# CAN-SW.net
KiCad netlist of a schematic drawn in Altium Designer
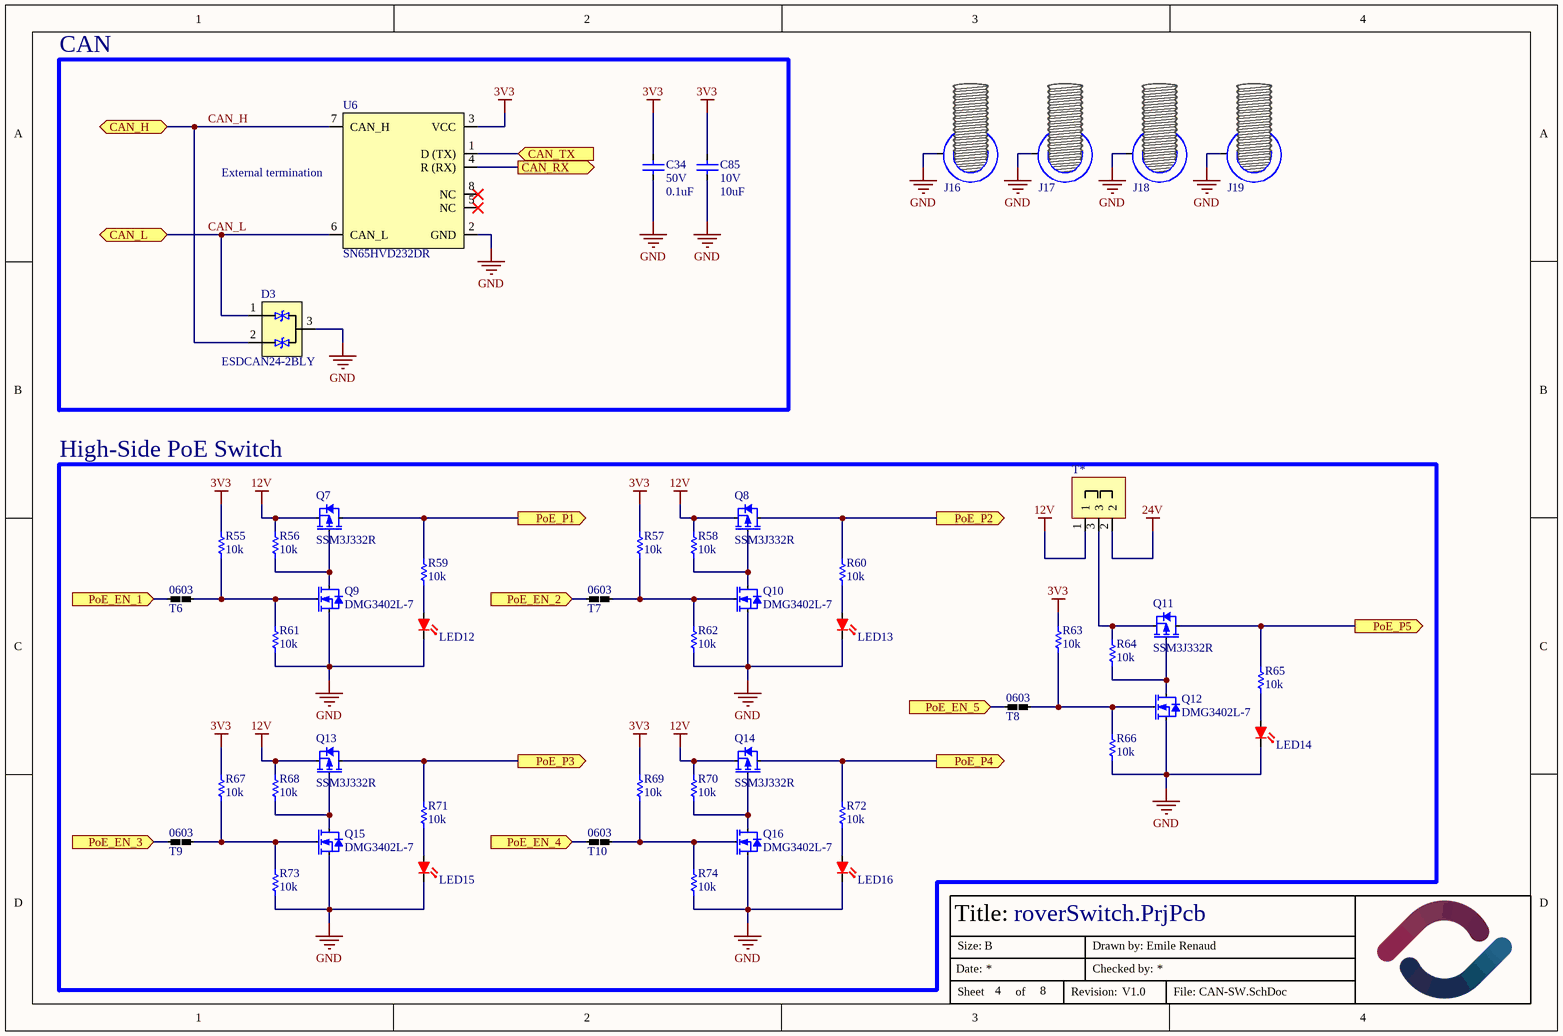
[diagram p0: CAN-SW.SchDoc]

(export (version "E")
  (design (tool "Eeschema 10.0.6"))
  (components
    (comp (ref "C34")
      (value "0.1uF")
      (footprint "CAPACITOR-0603")
      (description "Capacitor-0603-0.1uF-50V-X7R")
      (fields (field (name "VOLT") "50V"))
      (libsource (lib "Capacitors") (part "Capacitor-0603-0.1uF-50V-X7R"))
    )
    (comp (ref "C85")
      (value "10uF")
      (footprint "CAPACITOR-0603")
      (description "10 µF ±20% 10V Ceramic Capacitor X5R 0603 (1608 Metric)")
      (fields (field (name "VOLT") "10V") (field (name "Comment") "Capacitor-0603-10uF-10V-X5R"))
      (libsource (lib "Capacitors") (part "Capacitor-0603-10uF-10V-X5R"))
    )
    (comp (ref "D3")
      (value "ESDCAN24-2BLY")
      (footprint "SOT-23-3")
      (description "55V Clamp 6A (8/20µs) Ipp Tvs Diode Surface Mount SOT-23")
      (libsource (lib "diodes-tvs") (part "ESDCAN24-2BLY"))
    )
    (comp (ref "J16")
      (value "hole")
      (footprint "HOLE-3.40MM-M3-8MMEYELET")
      (description "Hole for M3 Bolt with 8mm pad")
      (libsource (lib "JumpersAndHoles") (part "Hole 3.40mm M3-Eyelet"))
    )
    (comp (ref "J17")
      (value "hole")
      (footprint "HOLE-3.40MM-M3-8MMEYELET")
      (description "Hole for M3 Bolt with 8mm pad")
      (libsource (lib "JumpersAndHoles") (part "Hole 3.40mm M3-Eyelet"))
    )
    (comp (ref "J18")
      (value "hole")
      (footprint "HOLE-3.40MM-M3-8MMEYELET")
      (description "Hole for M3 Bolt with 8mm pad")
      (libsource (lib "JumpersAndHoles") (part "Hole 3.40mm M3-Eyelet"))
    )
    (comp (ref "J19")
      (value "hole")
      (footprint "HOLE-3.40MM-M3-8MMEYELET")
      (description "Hole for M3 Bolt with 8mm pad")
      (libsource (lib "JumpersAndHoles") (part "Hole 3.40mm M3-Eyelet"))
    )
    (comp (ref "LED12")
      (value "B1911USD-20D000114U1930")
      (footprint "LED-0603-2PIN")
      (description "LED RED CLEAR 0603 SMD")
      (libsource (lib "LEDs") (part "B1911USD-20D000114U1930"))
    )
    (comp (ref "LED13")
      (value "B1911USD-20D000114U1930")
      (footprint "LED-0603-2PIN")
      (description "LED RED CLEAR 0603 SMD")
      (libsource (lib "LEDs") (part "B1911USD-20D000114U1930"))
    )
    (comp (ref "LED14")
      (value "B1911USD-20D000114U1930")
      (footprint "LED-0603-2PIN")
      (description "LED RED CLEAR 0603 SMD")
      (libsource (lib "LEDs") (part "B1911USD-20D000114U1930"))
    )
    (comp (ref "LED15")
      (value "B1911USD-20D000114U1930")
      (footprint "LED-0603-2PIN")
      (description "LED RED CLEAR 0603 SMD")
      (libsource (lib "LEDs") (part "B1911USD-20D000114U1930"))
    )
    (comp (ref "LED16")
      (value "B1911USD-20D000114U1930")
      (footprint "LED-0603-2PIN")
      (description "LED RED CLEAR 0603 SMD")
      (libsource (lib "LEDs") (part "B1911USD-20D000114U1930"))
    )
    (comp (ref "Q7")
      (value "SSM3J332R")
      (footprint "SOT-23-3")
      (description "P-Channel 30 V 6A (Ta) 1W (Ta) Surface Mount SOT-23F")
      (libsource (lib "FET-P-Small") (part "SSM3J332R"))
    )
    (comp (ref "Q8")
      (value "SSM3J332R")
      (footprint "SOT-23-3")
      (description "P-Channel 30 V 6A (Ta) 1W (Ta) Surface Mount SOT-23F")
      (libsource (lib "FET-P-Small") (part "SSM3J332R"))
    )
    (comp (ref "Q9")
      (value "DMG3402L-7")
      (footprint "SOT-23-3")
      (description "N-Channel 30 V 4A (Ta) 1.4W (Ta) Surface Mount SOT-23-3")
      (libsource (lib "FET-N-Small") (part "DMG3402L-7"))
    )
    (comp (ref "Q10")
      (value "DMG3402L-7")
      (footprint "SOT-23-3")
      (description "N-Channel 30 V 4A (Ta) 1.4W (Ta) Surface Mount SOT-23-3")
      (libsource (lib "FET-N-Small") (part "DMG3402L-7"))
    )
    (comp (ref "Q11")
      (value "SSM3J332R")
      (footprint "SOT-23-3")
      (description "P-Channel 30 V 6A (Ta) 1W (Ta) Surface Mount SOT-23F")
      (libsource (lib "FET-P-Small") (part "SSM3J332R"))
    )
    (comp (ref "Q12")
      (value "DMG3402L-7")
      (footprint "SOT-23-3")
      (description "N-Channel 30 V 4A (Ta) 1.4W (Ta) Surface Mount SOT-23-3")
      (libsource (lib "FET-N-Small") (part "DMG3402L-7"))
    )
    (comp (ref "Q13")
      (value "SSM3J332R")
      (footprint "SOT-23-3")
      (description "P-Channel 30 V 6A (Ta) 1W (Ta) Surface Mount SOT-23F")
      (libsource (lib "FET-P-Small") (part "SSM3J332R"))
    )
    (comp (ref "Q14")
      (value "SSM3J332R")
      (footprint "SOT-23-3")
      (description "P-Channel 30 V 6A (Ta) 1W (Ta) Surface Mount SOT-23F")
      (libsource (lib "FET-P-Small") (part "SSM3J332R"))
    )
    (comp (ref "Q15")
      (value "DMG3402L-7")
      (footprint "SOT-23-3")
      (description "N-Channel 30 V 4A (Ta) 1.4W (Ta) Surface Mount SOT-23-3")
      (libsource (lib "FET-N-Small") (part "DMG3402L-7"))
    )
    (comp (ref "Q16")
      (value "DMG3402L-7")
      (footprint "SOT-23-3")
      (description "N-Channel 30 V 4A (Ta) 1.4W (Ta) Surface Mount SOT-23-3")
      (libsource (lib "FET-N-Small") (part "DMG3402L-7"))
    )
    (comp (ref "R55")
      (value "10k")
      (footprint "Resistor-0603")
      (description "Resistor0603-10k")
      (fields (field (name "Comment") "SMT resistor"))
      (libsource (lib "Resistors") (part "Resistor-0603-10k"))
    )
    (comp (ref "R56")
      (value "10k")
      (footprint "Resistor-0603")
      (description "Resistor0603-10k")
      (fields (field (name "Comment") "SMT resistor"))
      (libsource (lib "Resistors") (part "Resistor-0603-10k"))
    )
    (comp (ref "R57")
      (value "10k")
      (footprint "Resistor-0603")
      (description "Resistor0603-10k")
      (fields (field (name "Comment") "SMT resistor"))
      (libsource (lib "Resistors") (part "Resistor-0603-10k"))
    )
    (comp (ref "R58")
      (value "10k")
      (footprint "Resistor-0603")
      (description "Resistor0603-10k")
      (fields (field (name "Comment") "SMT resistor"))
      (libsource (lib "Resistors") (part "Resistor-0603-10k"))
    )
    (comp (ref "R59")
      (value "10k")
      (footprint "Resistor-0603")
      (description "Resistor0603-10k")
      (fields (field (name "Comment") "SMT resistor"))
      (libsource (lib "Resistors") (part "Resistor-0603-10k"))
    )
    (comp (ref "R60")
      (value "10k")
      (footprint "Resistor-0603")
      (description "Resistor0603-10k")
      (fields (field (name "Comment") "SMT resistor"))
      (libsource (lib "Resistors") (part "Resistor-0603-10k"))
    )
    (comp (ref "R61")
      (value "10k")
      (footprint "Resistor-0603")
      (description "Resistor0603-10k")
      (fields (field (name "Comment") "SMT resistor"))
      (libsource (lib "Resistors") (part "Resistor-0603-10k"))
    )
    (comp (ref "R62")
      (value "10k")
      (footprint "Resistor-0603")
      (description "Resistor0603-10k")
      (fields (field (name "Comment") "SMT resistor"))
      (libsource (lib "Resistors") (part "Resistor-0603-10k"))
    )
    (comp (ref "R63")
      (value "10k")
      (footprint "Resistor-0603")
      (description "Resistor0603-10k")
      (fields (field (name "Comment") "SMT resistor"))
      (libsource (lib "Resistors") (part "Resistor-0603-10k"))
    )
    (comp (ref "R64")
      (value "10k")
      (footprint "Resistor-0603")
      (description "Resistor0603-10k")
      (fields (field (name "Comment") "SMT resistor"))
      (libsource (lib "Resistors") (part "Resistor-0603-10k"))
    )
    (comp (ref "R65")
      (value "10k")
      (footprint "Resistor-0603")
      (description "Resistor0603-10k")
      (fields (field (name "Comment") "SMT resistor"))
      (libsource (lib "Resistors") (part "Resistor-0603-10k"))
    )
    (comp (ref "R66")
      (value "10k")
      (footprint "Resistor-0603")
      (description "Resistor0603-10k")
      (fields (field (name "Comment") "SMT resistor"))
      (libsource (lib "Resistors") (part "Resistor-0603-10k"))
    )
    (comp (ref "R67")
      (value "10k")
      (footprint "Resistor-0603")
      (description "Resistor0603-10k")
      (fields (field (name "Comment") "SMT resistor"))
      (libsource (lib "Resistors") (part "Resistor-0603-10k"))
    )
    (comp (ref "R68")
      (value "10k")
      (footprint "Resistor-0603")
      (description "Resistor0603-10k")
      (fields (field (name "Comment") "SMT resistor"))
      (libsource (lib "Resistors") (part "Resistor-0603-10k"))
    )
    (comp (ref "R69")
      (value "10k")
      (footprint "Resistor-0603")
      (description "Resistor0603-10k")
      (fields (field (name "Comment") "SMT resistor"))
      (libsource (lib "Resistors") (part "Resistor-0603-10k"))
    )
    (comp (ref "R70")
      (value "10k")
      (footprint "Resistor-0603")
      (description "Resistor0603-10k")
      (fields (field (name "Comment") "SMT resistor"))
      (libsource (lib "Resistors") (part "Resistor-0603-10k"))
    )
    (comp (ref "R71")
      (value "10k")
      (footprint "Resistor-0603")
      (description "Resistor0603-10k")
      (fields (field (name "Comment") "SMT resistor"))
      (libsource (lib "Resistors") (part "Resistor-0603-10k"))
    )
    (comp (ref "R72")
      (value "10k")
      (footprint "Resistor-0603")
      (description "Resistor0603-10k")
      (fields (field (name "Comment") "SMT resistor"))
      (libsource (lib "Resistors") (part "Resistor-0603-10k"))
    )
    (comp (ref "R73")
      (value "10k")
      (footprint "Resistor-0603")
      (description "Resistor0603-10k")
      (fields (field (name "Comment") "SMT resistor"))
      (libsource (lib "Resistors") (part "Resistor-0603-10k"))
    )
    (comp (ref "R74")
      (value "10k")
      (footprint "Resistor-0603")
      (description "Resistor0603-10k")
      (fields (field (name "Comment") "SMT resistor"))
      (libsource (lib "Resistors") (part "Resistor-0603-10k"))
    )
    (comp (ref "T*")
      (value "Jumper-3pos-small")
      (footprint "Jumper-3pos-small")
      (libsource (lib "JumpersAndHoles") (part "Jumper-3pos-small"))
    )
    (comp (ref "T6")
      (value "NetTie_0603_Short")
      (footprint "NetTie-0603-short")
      (libsource (lib "JumpersAndHoles") (part "NetTie_0603_Short"))
    )
    (comp (ref "T7")
      (value "NetTie_0603_Short")
      (footprint "NetTie-0603-short")
      (libsource (lib "JumpersAndHoles") (part "NetTie_0603_Short"))
    )
    (comp (ref "T8")
      (value "NetTie_0603_Short")
      (footprint "NetTie-0603-short")
      (libsource (lib "JumpersAndHoles") (part "NetTie_0603_Short"))
    )
    (comp (ref "T9")
      (value "NetTie_0603_Short")
      (footprint "NetTie-0603-short")
      (libsource (lib "JumpersAndHoles") (part "NetTie_0603_Short"))
    )
    (comp (ref "T10")
      (value "NetTie_0603_Short")
      (footprint "NetTie-0603-short")
      (libsource (lib "JumpersAndHoles") (part "NetTie_0603_Short"))
    )
    (comp (ref "U6")
      (value "SN65HVD232DR")
      (footprint "SOIC-8")
      (description "1/1 Transceiver Half CANbus 8-SOIC")
      (libsource (lib "Transceiver") (part "SN65HVD232DR"))
    )
  )
  (nets
    (net (code "1") (name "/CAN_H") (class "Default")
      (node (ref "D3") (pin "2") (pinfunction "GND_2") (pintype "passive"))
      (node (ref "U6") (pin "7") (pinfunction "CAN_H_7") (pintype "passive"))
    )
    (net (code "2") (name "/CAN_L") (class "Default")
      (node (ref "D3") (pin "1") (pinfunction "L2_1") (pintype "passive"))
      (node (ref "U6") (pin "6") (pinfunction "CAN_L_6") (pintype "passive"))
    )
    (net (code "3") (name "/CAN_RX") (class "Default")
      (node (ref "U6") (pin "4") (pinfunction "R_(RX)_4") (pintype "passive"))
    )
    (net (code "4") (name "/CAN_TX") (class "Default")
      (node (ref "U6") (pin "1") (pinfunction "D_(TX)_1") (pintype "passive"))
    )
    (net (code "5") (name "/PoE_EN_1") (class "Default")
      (node (ref "T6") (pin "2") (pinfunction "2_2") (pintype "passive"))
    )
    (net (code "6") (name "/PoE_EN_2") (class "Default")
      (node (ref "T7") (pin "2") (pinfunction "2_2") (pintype "passive"))
    )
    (net (code "7") (name "/PoE_EN_3") (class "Default")
      (node (ref "T9") (pin "2") (pinfunction "2_2") (pintype "passive"))
    )
    (net (code "8") (name "/PoE_EN_4") (class "Default")
      (node (ref "T10") (pin "2") (pinfunction "2_2") (pintype "passive"))
    )
    (net (code "9") (name "/PoE_EN_5") (class "Default")
      (node (ref "T8") (pin "2") (pinfunction "2_2") (pintype "passive"))
    )
    (net (code "10") (name "/PoE_P1") (class "Default")
      (node (ref "Q7") (pin "3") (pinfunction "D_3") (pintype "passive"))
      (node (ref "R59") (pin "2") (pinfunction "2_2") (pintype "passive"))
    )
    (net (code "11") (name "/PoE_P2") (class "Default")
      (node (ref "Q8") (pin "3") (pinfunction "D_3") (pintype "passive"))
      (node (ref "R60") (pin "2") (pinfunction "2_2") (pintype "passive"))
    )
    (net (code "12") (name "/PoE_P3") (class "Default")
      (node (ref "Q13") (pin "3") (pinfunction "D_3") (pintype "passive"))
      (node (ref "R71") (pin "2") (pinfunction "2_2") (pintype "passive"))
    )
    (net (code "13") (name "/PoE_P4") (class "Default")
      (node (ref "Q14") (pin "3") (pinfunction "D_3") (pintype "passive"))
      (node (ref "R72") (pin "2") (pinfunction "2_2") (pintype "passive"))
    )
    (net (code "14") (name "/PoE_P5") (class "Default")
      (node (ref "Q11") (pin "3") (pinfunction "D_3") (pintype "passive"))
      (node (ref "R65") (pin "2") (pinfunction "2_2") (pintype "passive"))
    )
    (net (code "15") (name "3V3") (class "Default")
      (node (ref "C34") (pin "2") (pinfunction "2_2") (pintype "passive"))
      (node (ref "C85") (pin "2") (pinfunction "2_2") (pintype "passive"))
      (node (ref "R55") (pin "2") (pinfunction "2_2") (pintype "passive"))
      (node (ref "R57") (pin "2") (pinfunction "2_2") (pintype "passive"))
      (node (ref "R63") (pin "2") (pinfunction "2_2") (pintype "passive"))
      (node (ref "R67") (pin "2") (pinfunction "2_2") (pintype "passive"))
      (node (ref "R69") (pin "2") (pinfunction "2_2") (pintype "passive"))
      (node (ref "U6") (pin "3") (pinfunction "VCC_3") (pintype "passive"))
    )
    (net (code "16") (name "12V") (class "Default")
      (node (ref "Q13") (pin "2") (pinfunction "S_2") (pintype "passive"))
      (node (ref "Q14") (pin "2") (pinfunction "S_2") (pintype "passive"))
      (node (ref "Q7") (pin "2") (pinfunction "S_2") (pintype "passive"))
      (node (ref "Q8") (pin "2") (pinfunction "S_2") (pintype "passive"))
      (node (ref "R56") (pin "2") (pinfunction "2_2") (pintype "passive"))
      (node (ref "R58") (pin "2") (pinfunction "2_2") (pintype "passive"))
      (node (ref "R68") (pin "2") (pinfunction "2_2") (pintype "passive"))
      (node (ref "R70") (pin "2") (pinfunction "2_2") (pintype "passive"))
      (node (ref "T*") (pin "1") (pinfunction "1_1") (pintype "passive"))
    )
    (net (code "17") (name "24V") (class "Default")
      (node (ref "T*") (pin "2") (pinfunction "2_2") (pintype "passive"))
    )
    (net (code "18") (name "GND") (class "Default")
      (node (ref "C34") (pin "1") (pinfunction "1_1") (pintype "passive"))
      (node (ref "C85") (pin "1") (pinfunction "1_1") (pintype "passive"))
      (node (ref "D3") (pin "3") (pinfunction "L3_3") (pintype "passive"))
      (node (ref "J16") (pin "1") (pinfunction "1_1") (pintype "passive"))
      (node (ref "J17") (pin "1") (pinfunction "1_1") (pintype "passive"))
      (node (ref "J18") (pin "1") (pinfunction "1_1") (pintype "passive"))
      (node (ref "J19") (pin "1") (pinfunction "1_1") (pintype "passive"))
      (node (ref "LED12") (pin "1") (pinfunction "K_1") (pintype "passive"))
      (node (ref "LED13") (pin "1") (pinfunction "K_1") (pintype "passive"))
      (node (ref "LED14") (pin "1") (pinfunction "K_1") (pintype "passive"))
      (node (ref "LED15") (pin "1") (pinfunction "K_1") (pintype "passive"))
      (node (ref "LED16") (pin "1") (pinfunction "K_1") (pintype "passive"))
      (node (ref "Q10") (pin "2") (pinfunction "S_2") (pintype "passive"))
      (node (ref "Q12") (pin "2") (pinfunction "S_2") (pintype "passive"))
      (node (ref "Q15") (pin "2") (pinfunction "S_2") (pintype "passive"))
      (node (ref "Q16") (pin "2") (pinfunction "S_2") (pintype "passive"))
      (node (ref "Q9") (pin "2") (pinfunction "S_2") (pintype "passive"))
      (node (ref "R61") (pin "1") (pinfunction "1_1") (pintype "passive"))
      (node (ref "R62") (pin "1") (pinfunction "1_1") (pintype "passive"))
      (node (ref "R66") (pin "1") (pinfunction "1_1") (pintype "passive"))
      (node (ref "R73") (pin "1") (pinfunction "1_1") (pintype "passive"))
      (node (ref "R74") (pin "1") (pinfunction "1_1") (pintype "passive"))
      (node (ref "U6") (pin "2") (pinfunction "GND_2") (pintype "passive"))
    )
    (net (code "19") (name "Net-(LED12-R)") (class "Default")
      (node (ref "LED12") (pin "2") (pinfunction "R_2") (pintype "passive"))
      (node (ref "R59") (pin "1") (pinfunction "1_1") (pintype "passive"))
    )
    (net (code "20") (name "Net-(LED13-R)") (class "Default")
      (node (ref "LED13") (pin "2") (pinfunction "R_2") (pintype "passive"))
      (node (ref "R60") (pin "1") (pinfunction "1_1") (pintype "passive"))
    )
    (net (code "21") (name "Net-(LED14-R)") (class "Default")
      (node (ref "LED14") (pin "2") (pinfunction "R_2") (pintype "passive"))
      (node (ref "R65") (pin "1") (pinfunction "1_1") (pintype "passive"))
    )
    (net (code "22") (name "Net-(LED15-R)") (class "Default")
      (node (ref "LED15") (pin "2") (pinfunction "R_2") (pintype "passive"))
      (node (ref "R71") (pin "1") (pinfunction "1_1") (pintype "passive"))
    )
    (net (code "23") (name "Net-(LED16-R)") (class "Default")
      (node (ref "LED16") (pin "2") (pinfunction "R_2") (pintype "passive"))
      (node (ref "R72") (pin "1") (pinfunction "1_1") (pintype "passive"))
    )
    (net (code "24") (name "Net-(Q7-G)") (class "Default")
      (node (ref "Q7") (pin "1") (pinfunction "G_1") (pintype "passive"))
      (node (ref "Q9") (pin "3") (pinfunction "D_3") (pintype "passive"))
      (node (ref "R56") (pin "1") (pinfunction "1_1") (pintype "passive"))
    )
    (net (code "25") (name "Net-(Q9-G)") (class "Default")
      (node (ref "Q9") (pin "1") (pinfunction "G_1") (pintype "passive"))
      (node (ref "R55") (pin "1") (pinfunction "1_1") (pintype "passive"))
      (node (ref "R61") (pin "2") (pinfunction "2_2") (pintype "passive"))
      (node (ref "T6") (pin "1") (pinfunction "1_1") (pintype "passive"))
    )
    (net (code "26") (name "Net-(Q10-D)") (class "Default")
      (node (ref "Q10") (pin "3") (pinfunction "D_3") (pintype "passive"))
      (node (ref "Q8") (pin "1") (pinfunction "G_1") (pintype "passive"))
      (node (ref "R58") (pin "1") (pinfunction "1_1") (pintype "passive"))
    )
    (net (code "27") (name "Net-(Q10-G)") (class "Default")
      (node (ref "Q10") (pin "1") (pinfunction "G_1") (pintype "passive"))
      (node (ref "R57") (pin "1") (pinfunction "1_1") (pintype "passive"))
      (node (ref "R62") (pin "2") (pinfunction "2_2") (pintype "passive"))
      (node (ref "T7") (pin "1") (pinfunction "1_1") (pintype "passive"))
    )
    (net (code "28") (name "Net-(Q11-G)") (class "Default")
      (node (ref "Q11") (pin "1") (pinfunction "G_1") (pintype "passive"))
      (node (ref "Q12") (pin "3") (pinfunction "D_3") (pintype "passive"))
      (node (ref "R64") (pin "1") (pinfunction "1_1") (pintype "passive"))
    )
    (net (code "29") (name "Net-(Q11-S)") (class "Default")
      (node (ref "Q11") (pin "2") (pinfunction "S_2") (pintype "passive"))
      (node (ref "R64") (pin "2") (pinfunction "2_2") (pintype "passive"))
      (node (ref "T*") (pin "3") (pinfunction "3_3") (pintype "passive"))
    )
    (net (code "30") (name "Net-(Q12-G)") (class "Default")
      (node (ref "Q12") (pin "1") (pinfunction "G_1") (pintype "passive"))
      (node (ref "R63") (pin "1") (pinfunction "1_1") (pintype "passive"))
      (node (ref "R66") (pin "2") (pinfunction "2_2") (pintype "passive"))
      (node (ref "T8") (pin "1") (pinfunction "1_1") (pintype "passive"))
    )
    (net (code "31") (name "Net-(Q13-G)") (class "Default")
      (node (ref "Q13") (pin "1") (pinfunction "G_1") (pintype "passive"))
      (node (ref "Q15") (pin "3") (pinfunction "D_3") (pintype "passive"))
      (node (ref "R68") (pin "1") (pinfunction "1_1") (pintype "passive"))
    )
    (net (code "32") (name "Net-(Q14-G)") (class "Default")
      (node (ref "Q14") (pin "1") (pinfunction "G_1") (pintype "passive"))
      (node (ref "Q16") (pin "3") (pinfunction "D_3") (pintype "passive"))
      (node (ref "R70") (pin "1") (pinfunction "1_1") (pintype "passive"))
    )
    (net (code "33") (name "Net-(Q15-G)") (class "Default")
      (node (ref "Q15") (pin "1") (pinfunction "G_1") (pintype "passive"))
      (node (ref "R67") (pin "1") (pinfunction "1_1") (pintype "passive"))
      (node (ref "R73") (pin "2") (pinfunction "2_2") (pintype "passive"))
      (node (ref "T9") (pin "1") (pinfunction "1_1") (pintype "passive"))
    )
    (net (code "34") (name "Net-(Q16-G)") (class "Default")
      (node (ref "Q16") (pin "1") (pinfunction "G_1") (pintype "passive"))
      (node (ref "R69") (pin "1") (pinfunction "1_1") (pintype "passive"))
      (node (ref "R74") (pin "2") (pinfunction "2_2") (pintype "passive"))
      (node (ref "T10") (pin "1") (pinfunction "1_1") (pintype "passive"))
    )
    (net (code "35") (name "unconnected-(U6-NC-Pad5)") (class "Default")
      (node (ref "U6") (pin "5") (pinfunction "NC_5") (pintype "passive+no_connect"))
    )
    (net (code "36") (name "unconnected-(U6-NC-Pad8)") (class "Default")
      (node (ref "U6") (pin "8") (pinfunction "NC_8") (pintype "passive+no_connect"))
    )
  )
)
